# base.net
KiCad netlist of a schematic drawn in Altium Designer
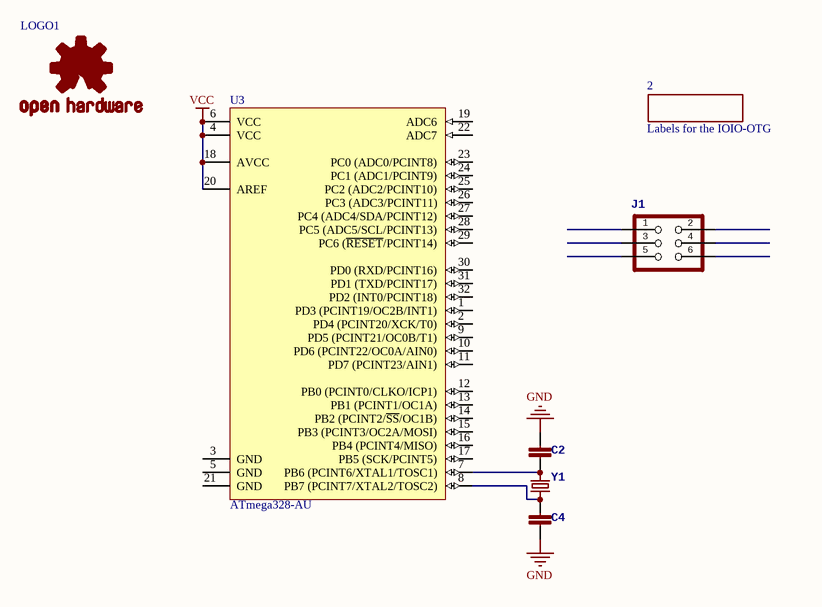
[diagram p0: base.SchDoc]

(export (version "E")
  (design (tool "Eeschema 10.0.6"))
  (components
    (comp (ref "2")
      (value "Labels for the IOIO-OTG")
      (footprint "IOIO-OTG-COPPER-EXPOSED")
      (libsource (lib "SparkFun-Aesthetics") (part "IOIO-OTG"))
    )
    (comp (ref "C2") (value "~") (footprint "C0805K") (libsource (lib "rcl") (part "C-EUC0805K")))
    (comp (ref "C4") (value "~") (footprint "C0805K") (libsource (lib "rcl") (part "C-EUC0805K")))
    (comp (ref "J1")
      (value "~")
      (footprint "2X3-NS")
      (libsource (lib "SparkFun-Connectors") (part "AVR_SPI_PRG_6NS"))
    )
    (comp (ref "LOGO1")
      (value "~")
      (footprint "OSHW-LOGO-L_COPPER")
      (libsource (lib "SparkFun-Aesthetics") (part "OSHW-LOGOL-COPPER"))
    )
    (comp (ref "U3")
      (value "ATmega328-AU")
      (footprint "32A_N")
      (libsource (lib "Atmel Microcontroller megaAVR") (part "ATmega328-AU"))
    )
    (comp (ref "Y1")
      (value "~")
      (footprint "HC49UP")
      (libsource (lib "SparkFun-FreqCtrl") (part "CRYSTALSMD"))
    )
  )
  (nets
    (net (code "1") (name "GND") (class "Default")
      (node (ref "C2") (pin "2") (pinfunction "2_2") (pintype "passive"))
      (node (ref "C4") (pin "1") (pinfunction "1_1") (pintype "passive"))
    )
    (net (code "2") (name "Net-(U3-PB6_(PCINT6{slash}XTAL1{slash}TOSC1))") (class "Default")
      (node (ref "C2") (pin "1") (pinfunction "1_1") (pintype "passive"))
      (node (ref "U3") (pin "7") (pinfunction "PB6_(PCINT6/XTAL1/TOSC1)_7") (pintype "bidirectional"))
      (node (ref "Y1") (pin "2") (pinfunction "2_2") (pintype "passive"))
    )
    (net (code "3") (name "Net-(U3-PB7_(PCINT7{slash}XTAL2{slash}TOSC2))") (class "Default")
      (node (ref "C4") (pin "2") (pinfunction "2_2") (pintype "passive"))
      (node (ref "U3") (pin "8") (pinfunction "PB7_(PCINT7/XTAL2/TOSC2)_8") (pintype "bidirectional"))
      (node (ref "Y1") (pin "1") (pinfunction "1_1") (pintype "passive"))
    )
    (net (code "4") (name "VCC") (class "Default")
      (node (ref "U3") (pin "18") (pinfunction "AVCC_18") (pintype "power_in"))
      (node (ref "U3") (pin "20") (pinfunction "AREF_20") (pintype "passive"))
      (node (ref "U3") (pin "4") (pinfunction "VCC_4") (pintype "power_in"))
      (node (ref "U3") (pin "6") (pinfunction "VCC_6") (pintype "power_in"))
    )
    (net (code "5") (name "unconnected-(J1-Pad1)") (class "Default")
      (node (ref "J1") (pin "1") (pinfunction "1_1") (pintype "passive"))
    )
    (net (code "6") (name "unconnected-(J1-Pad2)") (class "Default")
      (node (ref "J1") (pin "2") (pinfunction "2_2") (pintype "passive"))
    )
    (net (code "7") (name "unconnected-(J1-Pad3)") (class "Default")
      (node (ref "J1") (pin "3") (pinfunction "3_3") (pintype "passive"))
    )
    (net (code "8") (name "unconnected-(J1-Pad4)") (class "Default")
      (node (ref "J1") (pin "4") (pinfunction "4_4") (pintype "passive"))
    )
    (net (code "9") (name "unconnected-(J1-Pad5)") (class "Default")
      (node (ref "J1") (pin "5") (pinfunction "5_5") (pintype "passive"))
    )
    (net (code "10") (name "unconnected-(J1-Pad6)") (class "Default")
      (node (ref "J1") (pin "6") (pinfunction "6_6") (pintype "passive"))
    )
    (net (code "11") (name "unconnected-(U3-ADC6-Pad19)") (class "Default")
      (node (ref "U3") (pin "19") (pinfunction "ADC6_19") (pintype "input"))
    )
    (net (code "12") (name "unconnected-(U3-ADC7-Pad22)") (class "Default")
      (node (ref "U3") (pin "22") (pinfunction "ADC7_22") (pintype "input"))
    )
    (net (code "13") (name "unconnected-(U3-GND-Pad3)") (class "Default")
      (node (ref "U3") (pin "3") (pinfunction "GND_3") (pintype "power_in"))
    )
    (net (code "14") (name "unconnected-(U3-GND-Pad5)") (class "Default")
      (node (ref "U3") (pin "5") (pinfunction "GND_5") (pintype "power_in"))
    )
    (net (code "15") (name "unconnected-(U3-GND-Pad21)") (class "Default")
      (node (ref "U3") (pin "21") (pinfunction "GND_21") (pintype "power_in"))
    )
    (net (code "16") (name "unconnected-(U3-PB0_(PCINT0{slash}CLKO{slash}ICP1)-Pad12)") (class "Default")
      (node (ref "U3") (pin "12") (pinfunction "PB0_(PCINT0/CLKO/ICP1)_12") (pintype "bidirectional"))
    )
    (net (code "17") (name "unconnected-(U3-PB1_(PCINT1{slash}OC1A)-Pad13)") (class "Default")
      (node (ref "U3") (pin "13") (pinfunction "PB1_(PCINT1/OC1A)_13") (pintype "bidirectional"))
    )
    (net (code "18") (name "unconnected-(U3-PB2_(PCINT2{slash}~{SS}{slash}OC1B)-Pad14)") (class "Default")
      (node (ref "U3") (pin "14") (pinfunction "PB2_(PCINT2/~{SS}/OC1B)_14") (pintype "bidirectional"))
    )
    (net (code "19") (name "unconnected-(U3-PB3_(PCINT3{slash}OC2A{slash}MOSI)-Pad15)") (class "Default")
      (node (ref "U3") (pin "15") (pinfunction "PB3_(PCINT3/OC2A/MOSI)_15") (pintype "bidirectional"))
    )
    (net (code "20") (name "unconnected-(U3-PB4_(PCINT4{slash}MISO)-Pad16)") (class "Default")
      (node (ref "U3") (pin "16") (pinfunction "PB4_(PCINT4/MISO)_16") (pintype "bidirectional"))
    )
    (net (code "21") (name "unconnected-(U3-PB5_(SCK{slash}PCINT5)-Pad17)") (class "Default")
      (node (ref "U3") (pin "17") (pinfunction "PB5_(SCK/PCINT5)_17") (pintype "bidirectional"))
    )
    (net (code "22") (name "unconnected-(U3-PC0_(ADC0{slash}PCINT8)-Pad23)") (class "Default")
      (node (ref "U3") (pin "23") (pinfunction "PC0_(ADC0/PCINT8)_23") (pintype "bidirectional"))
    )
    (net (code "23") (name "unconnected-(U3-PC1_(ADC1{slash}PCINT9)-Pad24)") (class "Default")
      (node (ref "U3") (pin "24") (pinfunction "PC1_(ADC1/PCINT9)_24") (pintype "bidirectional"))
    )
    (net (code "24") (name "unconnected-(U3-PC2_(ADC2{slash}PCINT10)-Pad25)") (class "Default")
      (node (ref "U3") (pin "25") (pinfunction "PC2_(ADC2/PCINT10)_25") (pintype "bidirectional"))
    )
    (net (code "25") (name "unconnected-(U3-PC3_(ADC3{slash}PCINT11)-Pad26)") (class "Default")
      (node (ref "U3") (pin "26") (pinfunction "PC3_(ADC3/PCINT11)_26") (pintype "bidirectional"))
    )
    (net (code "26") (name "unconnected-(U3-PC4_(ADC4{slash}SDA{slash}PCINT12)-Pad27)") (class "Default")
      (node (ref "U3") (pin "27") (pinfunction "PC4_(ADC4/SDA/PCINT12)_27") (pintype "bidirectional"))
    )
    (net (code "27") (name "unconnected-(U3-PC5_(ADC5{slash}SCL{slash}PCINT13)-Pad28)") (class "Default")
      (node (ref "U3") (pin "28") (pinfunction "PC5_(ADC5/SCL/PCINT13)_28") (pintype "bidirectional"))
    )
    (net (code "28") (name "unconnected-(U3-PC6_(~{RESET}{slash}PCINT14)-Pad29)") (class "Default")
      (node (ref "U3") (pin "29") (pinfunction "PC6_(~{RESET}/PCINT14)_29") (pintype "bidirectional"))
    )
    (net (code "29") (name "unconnected-(U3-PD0_(RXD{slash}PCINT16)-Pad30)") (class "Default")
      (node (ref "U3") (pin "30") (pinfunction "PD0_(RXD/PCINT16)_30") (pintype "bidirectional"))
    )
    (net (code "30") (name "unconnected-(U3-PD1_(TXD{slash}PCINT17)-Pad31)") (class "Default")
      (node (ref "U3") (pin "31") (pinfunction "PD1_(TXD/PCINT17)_31") (pintype "bidirectional"))
    )
    (net (code "31") (name "unconnected-(U3-PD2_(INT0{slash}PCINT18)-Pad32)") (class "Default")
      (node (ref "U3") (pin "32") (pinfunction "PD2_(INT0/PCINT18)_32") (pintype "bidirectional"))
    )
    (net (code "32") (name "unconnected-(U3-PD3_(PCINT19{slash}OC2B{slash}INT1)-Pad1)") (class "Default")
      (node (ref "U3") (pin "1") (pinfunction "PD3_(PCINT19/OC2B/INT1)_1") (pintype "bidirectional"))
    )
    (net (code "33") (name "unconnected-(U3-PD4_(PCINT20{slash}XCK{slash}T0)-Pad2)") (class "Default")
      (node (ref "U3") (pin "2") (pinfunction "PD4_(PCINT20/XCK/T0)_2") (pintype "bidirectional"))
    )
    (net (code "34") (name "unconnected-(U3-PD5_(PCINT21{slash}OC0B{slash}T1)-Pad9)") (class "Default")
      (node (ref "U3") (pin "9") (pinfunction "PD5_(PCINT21/OC0B/T1)_9") (pintype "bidirectional"))
    )
    (net (code "35") (name "unconnected-(U3-PD6_(PCINT22{slash}OC0A{slash}AIN0)-Pad10)") (class "Default")
      (node (ref "U3") (pin "10") (pinfunction "PD6_(PCINT22/OC0A/AIN0)_10") (pintype "bidirectional"))
    )
    (net (code "36") (name "unconnected-(U3-PD7_(PCINT23{slash}AIN1)-Pad11)") (class "Default")
      (node (ref "U3") (pin "11") (pinfunction "PD7_(PCINT23/AIN1)_11") (pintype "bidirectional"))
    )
  )
)
